# ProProject__V1_1_02_2023-12-25.net
KiCad netlist of a schematic drawn in EasyEDA Pro
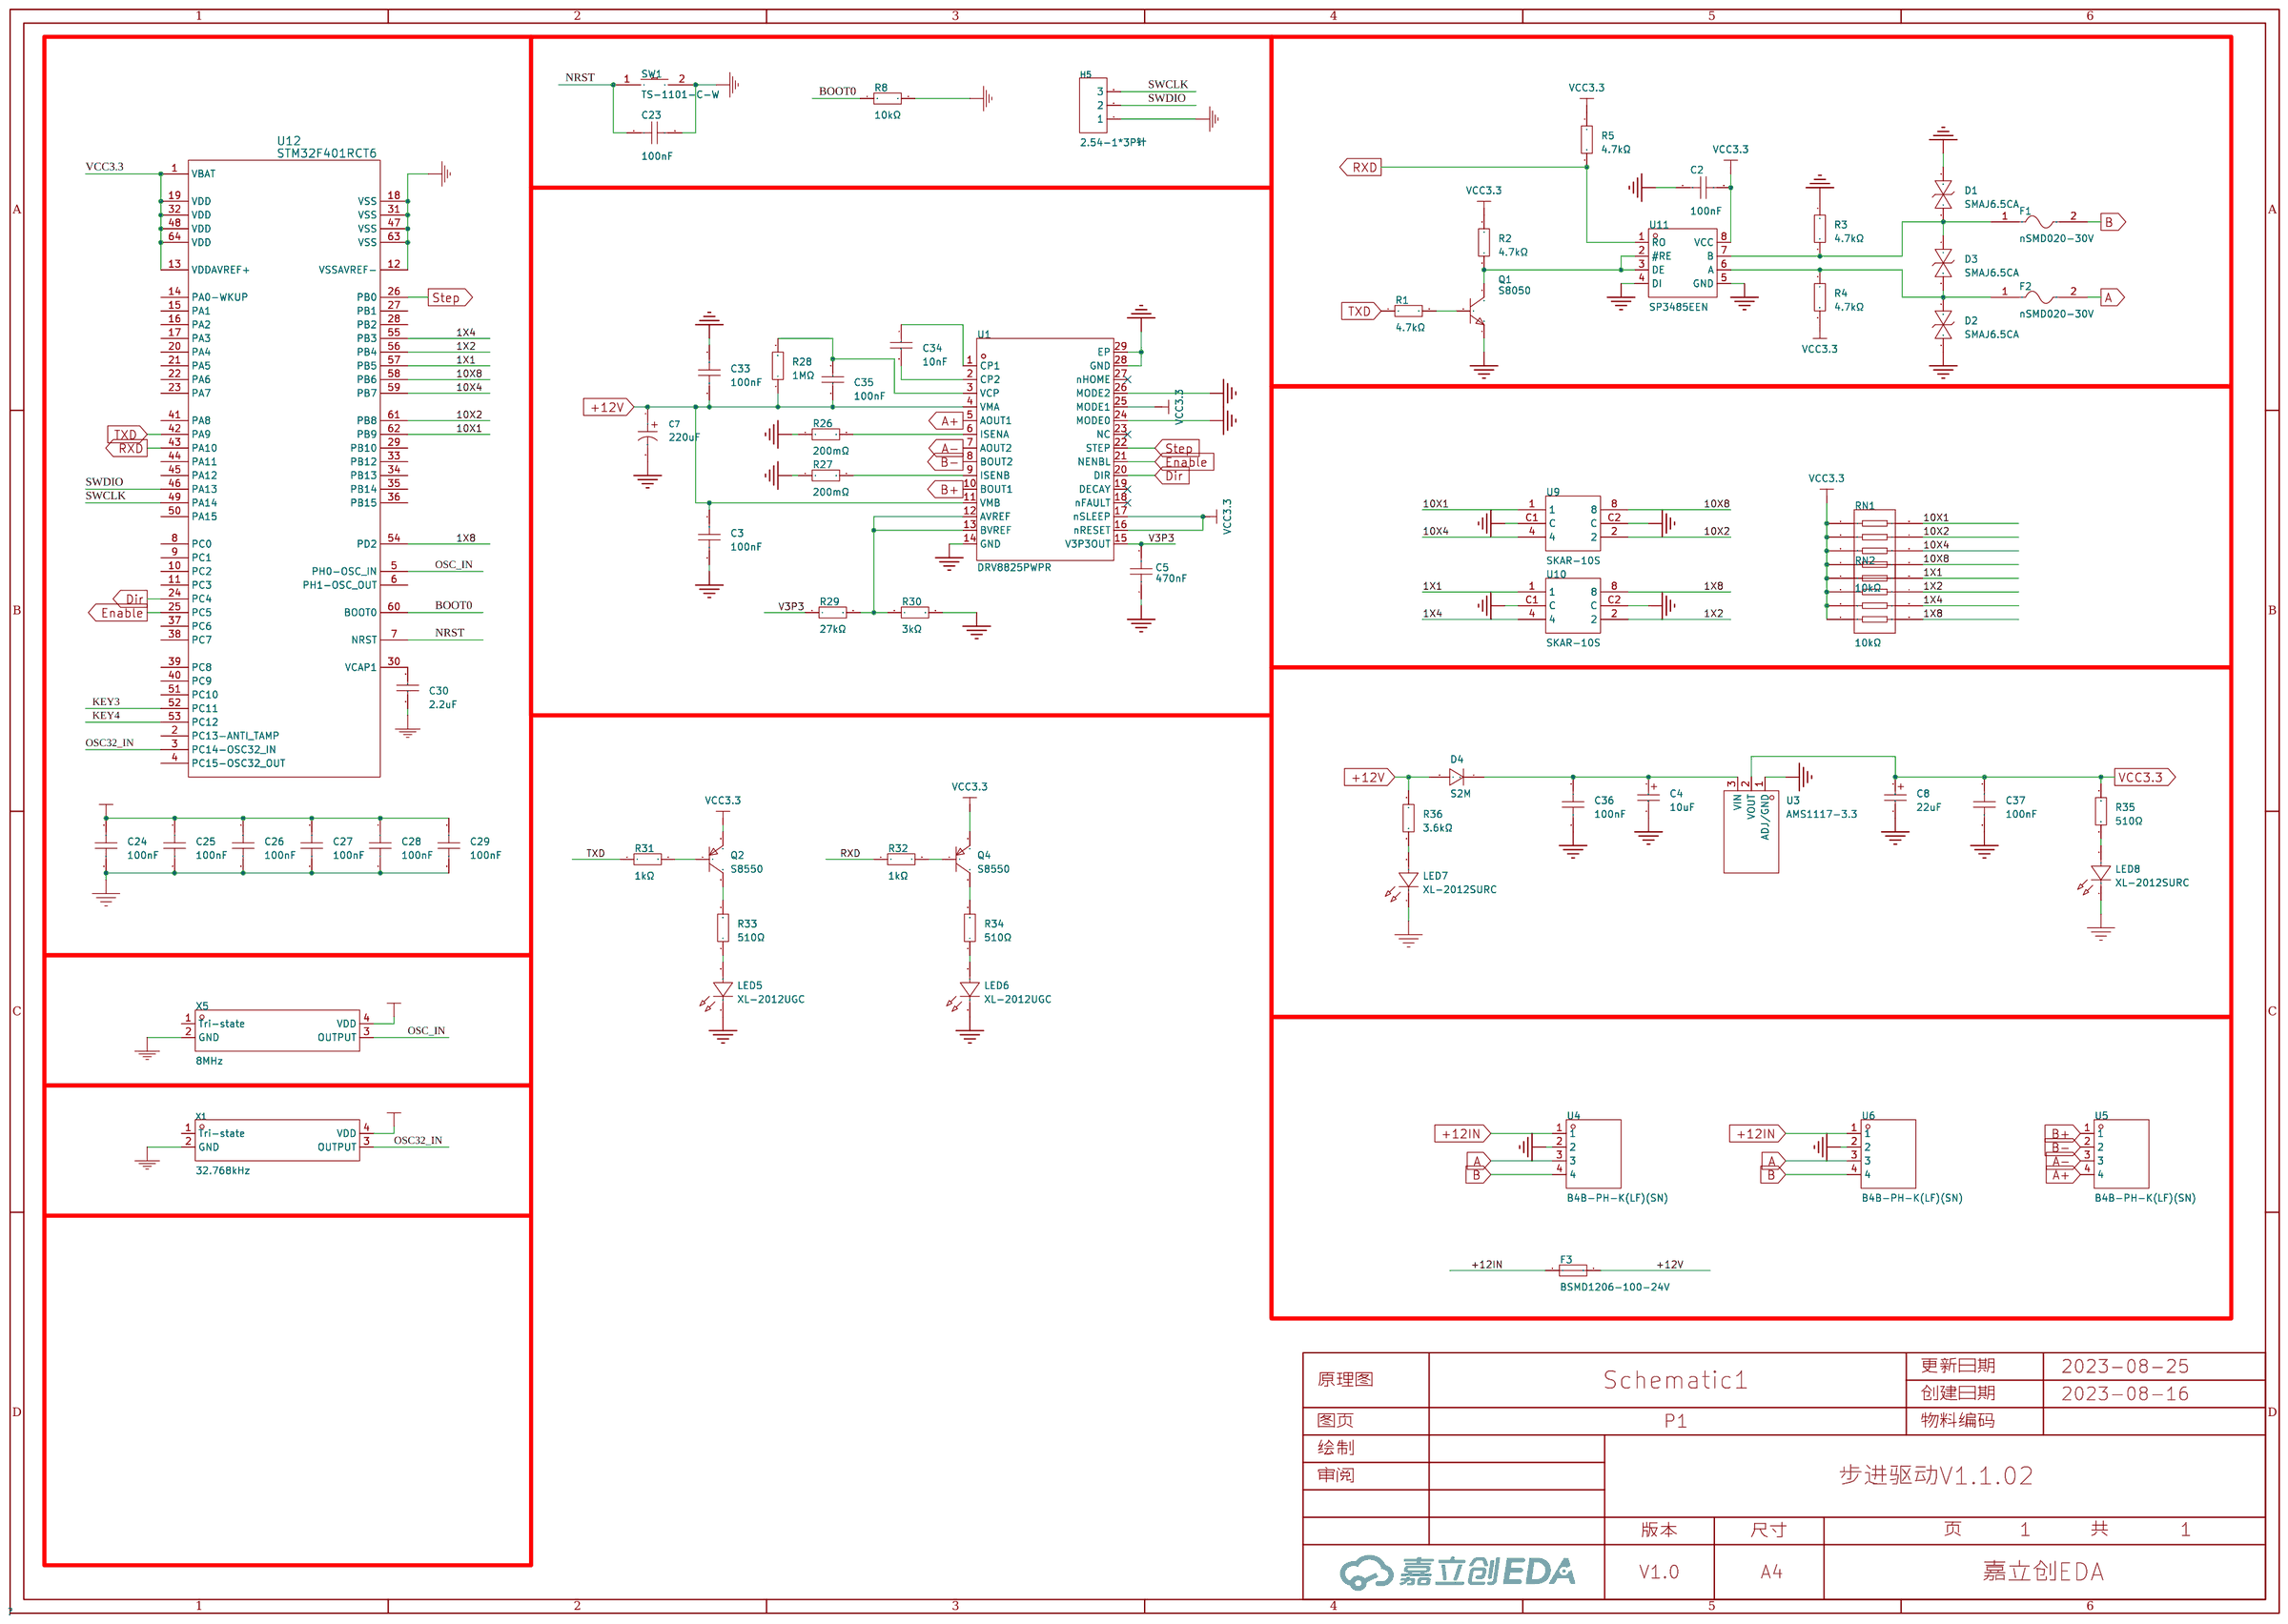
[diagram p0: schematic sheet]

(export (version "E")
  (design (tool "Eeschema 10.0.6"))
  (components
    (comp (ref "C2")
      (value "100nF")
      (footprint "easyedapro:C0603")
      (description "容值:100nF;精度:±10%;额定电压:50V;材质(温度系数):X7R;")
      (fields
        (field (name "Manufacturer Part") "CC0603KRX7R9BB104")
        (field (name "Manufacturer") "YAGEO(国巨)")
      )
      (libsource (lib "easyedapro") (part "CC0603KRX7R9BB104"))
    )
    (comp (ref "C3")
      (value "100nF")
      (footprint "easyedapro:C0603")
      (description "容值:100nF;精度:±10%;额定电压:50V;材质(温度系数):X7R;")
      (fields
        (field (name "Manufacturer Part") "CC0603KRX7R9BB104")
        (field (name "Manufacturer") "YAGEO(国巨)")
      )
      (libsource (lib "easyedapro") (part "CC0603KRX7R9BB104"))
    )
    (comp (ref "C4")
      (value "10uF")
      (footprint "easyedapro:CAP-SMD_L3.2-W1.6-RD")
      (description "容值:10uF;精度:±10%;额定电压:16V;等效串联电阻:10Ω@100kHz;")
      (fields
        (field (name "Manufacturer Part") "CA45-A-16V-10uF-K")
        (field (name "Manufacturer") "CEC(振华新云)")
      )
      (libsource (lib "easyedapro") (part "CA45-A-16V-10UF-K"))
    )
    (comp (ref "C5")
      (value "470nF")
      (footprint "easyedapro:C0603")
      (description "容值:470nF;精度:±10%;额定电压:6.3V;材质(温度系数):X5R;")
      (fields
        (field (name "Manufacturer Part") "CC0603KRX5R5BB474")
        (field (name "Manufacturer") "YAGEO(国巨)")
      )
      (libsource (lib "easyedapro") (part "CC0603KRX5R5BB474"))
    )
    (comp (ref "C7")
      (value "220uF")
      (footprint "easyedapro:CAP-SMD_BD6.3-L6.6-W6.6-FD")
      (description "容值:220uF;精度:±20%;额定电压:16V;纹波电流:110mA@120Hz;等效串联电阻:-;")
      (fields
        (field (name "Manufacturer Part") "RVT220UF16V67RV0015")
        (field (name "Manufacturer") "KNSCHA(科尼盛)")
      )
      (libsource (lib "easyedapro") (part "RVT220UF16V67RV0015"))
    )
    (comp (ref "C8")
      (value "22uF")
      (footprint "easyedapro:CAP-SMD_L3.5-W2.8-R-RD")
      (description "容值:22uF;精度:±10%;额定电压:16V;等效串联电阻:2.2Ω@100kHz;")
      (fields (field (name "Manufacturer Part") "CA45-B016K226T") (field (name "Manufacturer") "湘怡中元/湘江"))
      (libsource (lib "easyedapro") (part "CA45-B016K226T"))
    )
    (comp (ref "C23")
      (value "100nF")
      (footprint "easyedapro:C0603")
      (description "容值:100nF;精度:±10%;额定电压:50V;材质(温度系数):X7R;")
      (fields
        (field (name "Manufacturer Part") "CC0603KRX7R9BB104")
        (field (name "Manufacturer") "YAGEO(国巨)")
      )
      (libsource (lib "easyedapro") (part "CC0603KRX7R9BB104"))
    )
    (comp (ref "C24")
      (value "100nF")
      (footprint "easyedapro:C0603")
      (description "容值:100nF;精度:±10%;额定电压:50V;材质(温度系数):X7R;")
      (fields
        (field (name "Manufacturer Part") "CC0603KRX7R9BB104")
        (field (name "Manufacturer") "YAGEO(国巨)")
      )
      (libsource (lib "easyedapro") (part "CC0603KRX7R9BB104"))
    )
    (comp (ref "C25")
      (value "100nF")
      (footprint "easyedapro:C0603")
      (description "容值:100nF;精度:±10%;额定电压:50V;材质(温度系数):X7R;")
      (fields
        (field (name "Manufacturer Part") "CC0603KRX7R9BB104")
        (field (name "Manufacturer") "YAGEO(国巨)")
      )
      (libsource (lib "easyedapro") (part "CC0603KRX7R9BB104"))
    )
    (comp (ref "C26")
      (value "100nF")
      (footprint "easyedapro:C0603")
      (description "容值:100nF;精度:±10%;额定电压:50V;材质(温度系数):X7R;")
      (fields
        (field (name "Manufacturer Part") "CC0603KRX7R9BB104")
        (field (name "Manufacturer") "YAGEO(国巨)")
      )
      (libsource (lib "easyedapro") (part "CC0603KRX7R9BB104"))
    )
    (comp (ref "C27")
      (value "100nF")
      (footprint "easyedapro:C0603")
      (description "容值:100nF;精度:±10%;额定电压:50V;材质(温度系数):X7R;")
      (fields
        (field (name "Manufacturer Part") "CC0603KRX7R9BB104")
        (field (name "Manufacturer") "YAGEO(国巨)")
      )
      (libsource (lib "easyedapro") (part "CC0603KRX7R9BB104"))
    )
    (comp (ref "C28")
      (value "100nF")
      (footprint "easyedapro:C0603")
      (description "容值:100nF;精度:±10%;额定电压:50V;材质(温度系数):X7R;")
      (fields
        (field (name "Manufacturer Part") "CC0603KRX7R9BB104")
        (field (name "Manufacturer") "YAGEO(国巨)")
      )
      (libsource (lib "easyedapro") (part "CC0603KRX7R9BB104"))
    )
    (comp (ref "C29")
      (value "100nF")
      (footprint "easyedapro:C0603")
      (description "容值:100nF;精度:±10%;额定电压:50V;材质(温度系数):X7R;")
      (fields
        (field (name "Manufacturer Part") "CC0603KRX7R9BB104")
        (field (name "Manufacturer") "YAGEO(国巨)")
      )
      (libsource (lib "easyedapro") (part "CC0603KRX7R9BB104"))
    )
    (comp (ref "C30")
      (value "2.2uF")
      (footprint "easyedapro:C0603")
      (description "容值:2.2uF;精度:±10%;额定电压:25V;材质(温度系数):X7R;")
      (fields (field (name "Manufacturer Part") "0603B225K250NT") (field (name "Manufacturer") "FH(风华)"))
      (libsource (lib "easyedapro") (part "0603B225K250NT"))
    )
    (comp (ref "C33")
      (value "100nF")
      (footprint "easyedapro:C0603")
      (description "容值:100nF;精度:±10%;额定电压:50V;材质(温度系数):X7R;")
      (fields
        (field (name "Manufacturer Part") "CC0603KRX7R9BB104")
        (field (name "Manufacturer") "YAGEO(国巨)")
      )
      (libsource (lib "easyedapro") (part "CC0603KRX7R9BB104"))
    )
    (comp (ref "C34")
      (value "10nF")
      (footprint "easyedapro:C0603")
      (description "容值:10nF;精度:±10%;额定电压:50V;材质(温度系数):X7R;")
      (fields
        (field (name "Manufacturer Part") "CC0603KRX7R9BB103")
        (field (name "Manufacturer") "YAGEO(国巨)")
      )
      (libsource (lib "easyedapro") (part "CC0603KRX7R9BB103"))
    )
    (comp (ref "C35")
      (value "100nF")
      (footprint "easyedapro:C0603")
      (description "容值:100nF;精度:±10%;额定电压:16V;材质(温度系数):X7R;")
      (fields
        (field (name "Manufacturer Part") "CL10B104KO8NNNC")
        (field (name "Manufacturer") "SAMSUNG(三星)")
      )
      (libsource (lib "easyedapro") (part "CL10B104KO8NNNC"))
    )
    (comp (ref "C36")
      (value "100nF")
      (footprint "easyedapro:C0603")
      (description "容值:100nF;精度:±10%;额定电压:50V;材质(温度系数):X7R;")
      (fields
        (field (name "Manufacturer Part") "CC0603KRX7R9BB104")
        (field (name "Manufacturer") "YAGEO(国巨)")
      )
      (libsource (lib "easyedapro") (part "CC0603KRX7R9BB104"))
    )
    (comp (ref "C37")
      (value "100nF")
      (footprint "easyedapro:C0603")
      (description "容值:100nF;精度:±10%;额定电压:50V;材质(温度系数):X7R;")
      (fields
        (field (name "Manufacturer Part") "CC0603KRX7R9BB104")
        (field (name "Manufacturer") "YAGEO(国巨)")
      )
      (libsource (lib "easyedapro") (part "CC0603KRX7R9BB104"))
    )
    (comp (ref "D1")
      (value "SMAJ6.5CA")
      (footprint "easyedapro:SMA_L4.3-W2.5-LS5.0-BI")
      (description "极性:双向;")
      (fields (field (name "Manufacturer") "TWGMC(台湾迪嘉)"))
      (libsource (lib "easyedapro") (part "SMAJ6.5CA_C726773"))
    )
    (comp (ref "D2")
      (value "SMAJ6.5CA")
      (footprint "easyedapro:SMA_L4.3-W2.5-LS5.0-BI")
      (description "极性:双向;")
      (fields (field (name "Manufacturer") "TWGMC(台湾迪嘉)"))
      (libsource (lib "easyedapro") (part "SMAJ6.5CA_C726773"))
    )
    (comp (ref "D3")
      (value "SMAJ6.5CA")
      (footprint "easyedapro:SMA_L4.3-W2.5-LS5.0-BI")
      (description "极性:双向;")
      (fields (field (name "Manufacturer") "TWGMC(台湾迪嘉)"))
      (libsource (lib "easyedapro") (part "SMAJ6.5CA_C726773"))
    )
    (comp (ref "D4")
      (value "S2M")
      (footprint "easyedapro:SMA_L4.4-W2.8-LS5.4-RD")
      (description "二极管配置:-;直流反向耐压(Vr):1kV;平均整流电流(Io):2A;正向压降(Vf):1.1V@2A;反向电流(Ir):5uA@1kV;")
      (fields (field (name "Manufacturer") "MDD"))
      (libsource (lib "easyedapro") (part "S2M-C18905"))
    )
    (comp (ref "F1")
      (value "nSMD020-30V")
      (footprint "easyedapro:F1206")
      (description "最大电压:30V;最大电流:100A;保持电流:200mA;跳闸电流:460mA;")
      (fields (field (name "Manufacturer") "台湾陆海"))
      (libsource (lib "easyedapro") (part "nSMD020-30V"))
    )
    (comp (ref "F2")
      (value "nSMD020-30V")
      (footprint "easyedapro:F1206")
      (description "最大电压:30V;最大电流:100A;保持电流:200mA;跳闸电流:460mA;")
      (fields (field (name "Manufacturer") "台湾陆海"))
      (libsource (lib "easyedapro") (part "nSMD020-30V"))
    )
    (comp (ref "F3")
      (value "BSMD1206-100-24V")
      (footprint "easyedapro:F1206")
      (fields (field (name "Manufacturer") "BHFUSE(佰宏)"))
      (libsource (lib "easyedapro") (part "BSMD1206-100-24V"))
    )
    (comp (ref "H5")
      (value "2.54-1*3P针")
      (footprint "easyedapro:HDR-TH_3P-P2.54-V-M-1")
      (fields (field (name "Manufacturer") "BOOMELE(博穆精密)"))
      (libsource (lib "easyedapro") (part "Header-Male-2.54_1x3"))
    )
    (comp (ref "LED5")
      (value "XL-2012UGC")
      (footprint "easyedapro:LED0805-RD_GREEN")
      (description "发光颜色:翠绿;主波长:516nm~525nm;色温:-;功率:80mW;安装方式:正贴;")
      (fields (field (name "Manufacturer") "XINGLIGHT(成兴光)"))
      (libsource (lib "easyedapro") (part "XL-2012UGC"))
    )
    (comp (ref "LED6")
      (value "XL-2012UGC")
      (footprint "easyedapro:LED0805-RD_GREEN")
      (description "发光颜色:翠绿;主波长:516nm~525nm;色温:-;功率:80mW;安装方式:正贴;")
      (fields (field (name "Manufacturer") "XINGLIGHT(成兴光)"))
      (libsource (lib "easyedapro") (part "XL-2012UGC"))
    )
    (comp (ref "LED7")
      (value "XL-2012SURC")
      (footprint "easyedapro:LED0805-RD_RED")
      (description "发光颜色:红灯;主波长:617nm~621nm;色温:-;功率:55mW;安装方式:正贴;")
      (fields (field (name "Manufacturer") "XINGLIGHT(成兴光)"))
      (libsource (lib "easyedapro") (part "XL-2012SURC"))
    )
    (comp (ref "LED8")
      (value "XL-2012SURC")
      (footprint "easyedapro:LED0805-RD_RED")
      (description "发光颜色:红灯;主波长:617nm~621nm;色温:-;功率:55mW;安装方式:正贴;")
      (fields (field (name "Manufacturer") "XINGLIGHT(成兴光)"))
      (libsource (lib "easyedapro") (part "XL-2012SURC"))
    )
    (comp (ref "Q1")
      (value "S8050")
      (footprint "easyedapro:SOT-23-3_L2.9-W1.6-P1.90-LS2.8-BR")
      (description "晶体管类型:NPN;集射极击穿电压(Vceo):25V;集电极电流(Ic):500mA;功率(Pd):300mW;直流电流增益(hFE@Ic,Vce):120@50mA,1V;")
      (fields (field (name "Manufacturer") "CJ(江苏长电/长晶)"))
      (libsource (lib "easyedapro") (part "S8050_C105433"))
    )
    (comp (ref "Q2")
      (value "S8550")
      (footprint "easyedapro:SOT-23-3_L2.9-W1.6-P1.90-LS2.8-BR")
      (description "晶体管类型:PNP;集射极击穿电压(Vceo):25V;集电极电流(Ic):500mA;功率(Pd):300mW;直流电流增益(hFE@Ic,Vce):120@50mA,1V;")
      (fields (field (name "Manufacturer") "CJ(江苏长电/长晶)"))
      (libsource (lib "easyedapro") (part "S8550_C105432"))
    )
    (comp (ref "Q4")
      (value "S8550")
      (footprint "easyedapro:SOT-23-3_L2.9-W1.6-P1.90-LS2.8-BR")
      (description "晶体管类型:PNP;集射极击穿电压(Vceo):25V;集电极电流(Ic):500mA;功率(Pd):300mW;直流电流增益(hFE@Ic,Vce):120@50mA,1V;")
      (fields (field (name "Manufacturer") "CJ(江苏长电/长晶)"))
      (libsource (lib "easyedapro") (part "S8550_C105432"))
    )
    (comp (ref "R1")
      (value "4.7kΩ")
      (footprint "easyedapro:R0603")
      (description "电阻类型:厚膜电阻;阻值:4.7kΩ;精度:±1%;功率:100mW;")
      (fields
        (field (name "Manufacturer Part") "0603WAF4701T5E")
        (field (name "Manufacturer") "UNI-ROYAL(厚声)")
      )
      (libsource (lib "easyedapro") (part "0603WAF4701T5E"))
    )
    (comp (ref "R2")
      (value "4.7kΩ")
      (footprint "easyedapro:R0603")
      (description "电阻类型:厚膜电阻;阻值:4.7kΩ;精度:±1%;功率:100mW;")
      (fields
        (field (name "Manufacturer Part") "0603WAF4701T5E")
        (field (name "Manufacturer") "UNI-ROYAL(厚声)")
      )
      (libsource (lib "easyedapro") (part "0603WAF4701T5E"))
    )
    (comp (ref "R3")
      (value "4.7kΩ")
      (footprint "easyedapro:R0603")
      (description "电阻类型:厚膜电阻;阻值:4.7kΩ;精度:±1%;功率:100mW;")
      (fields
        (field (name "Manufacturer Part") "0603WAF4701T5E")
        (field (name "Manufacturer") "UNI-ROYAL(厚声)")
      )
      (libsource (lib "easyedapro") (part "0603WAF4701T5E"))
    )
    (comp (ref "R4")
      (value "4.7kΩ")
      (footprint "easyedapro:R0603")
      (description "电阻类型:厚膜电阻;阻值:4.7kΩ;精度:±1%;功率:100mW;")
      (fields
        (field (name "Manufacturer Part") "0603WAF4701T5E")
        (field (name "Manufacturer") "UNI-ROYAL(厚声)")
      )
      (libsource (lib "easyedapro") (part "0603WAF4701T5E"))
    )
    (comp (ref "R5")
      (value "4.7kΩ")
      (footprint "easyedapro:R0603")
      (description "电阻类型:厚膜电阻;阻值:4.7kΩ;精度:±1%;功率:100mW;")
      (fields
        (field (name "Manufacturer Part") "0603WAF4701T5E")
        (field (name "Manufacturer") "UNI-ROYAL(厚声)")
      )
      (libsource (lib "easyedapro") (part "0603WAF4701T5E"))
    )
    (comp (ref "R8")
      (value "10kΩ")
      (footprint "easyedapro:R0603")
      (description "电阻类型:厚膜电阻;阻值:10kΩ;精度:±1%;功率:100mW;")
      (fields
        (field (name "Manufacturer Part") "0603WAF1002T5E")
        (field (name "Manufacturer") "UNI-ROYAL(厚声)")
      )
      (libsource (lib "easyedapro") (part "0603WAF1002T5E"))
    )
    (comp (ref "R26")
      (value "200mΩ")
      (footprint "easyedapro:R0603")
      (description "电阻类型:厚膜电阻;阻值:200mΩ;精度:±1%;功率:100mW;")
      (fields
        (field (name "Manufacturer Part") "0603WAF200LT5E")
        (field (name "Manufacturer") "UNI-ROYAL(厚声)")
      )
      (libsource (lib "easyedapro") (part "0603WAF200LT5E"))
    )
    (comp (ref "R27")
      (value "200mΩ")
      (footprint "easyedapro:R0603")
      (description "电阻类型:厚膜电阻;阻值:200mΩ;精度:±1%;功率:100mW;")
      (fields
        (field (name "Manufacturer Part") "0603WAF200LT5E")
        (field (name "Manufacturer") "UNI-ROYAL(厚声)")
      )
      (libsource (lib "easyedapro") (part "0603WAF200LT5E"))
    )
    (comp (ref "R28")
      (value "1MΩ")
      (footprint "easyedapro:R0603")
      (description "电阻类型:厚膜电阻;阻值:1MΩ;精度:±1%;功率:100mW;")
      (fields
        (field (name "Manufacturer Part") "0603WAF1004T5E")
        (field (name "Manufacturer") "UNI-ROYAL(厚声)")
      )
      (libsource (lib "easyedapro") (part "0603WAF1004T5E"))
    )
    (comp (ref "R29")
      (value "27kΩ")
      (footprint "easyedapro:R0603")
      (description "电阻类型:厚膜电阻;阻值:27kΩ;精度:±1%;功率:100mW;")
      (fields
        (field (name "Manufacturer Part") "0603WAF2702T5E")
        (field (name "Manufacturer") "UNI-ROYAL(厚声)")
      )
      (libsource (lib "easyedapro") (part "0603WAF2702T5E"))
    )
    (comp (ref "R30")
      (value "3kΩ")
      (footprint "easyedapro:R0603")
      (description "电阻类型:厚膜电阻;阻值:3kΩ;精度:±1%;功率:100mW;")
      (fields
        (field (name "Manufacturer Part") "0603WAF3001T5E")
        (field (name "Manufacturer") "UNI-ROYAL(厚声)")
      )
      (libsource (lib "easyedapro") (part "0603WAF3001T5E"))
    )
    (comp (ref "R31")
      (value "1kΩ")
      (footprint "easyedapro:R0603")
      (description "电阻类型:厚膜电阻;阻值:1kΩ;精度:±1%;功率:100mW;")
      (fields
        (field (name "Manufacturer Part") "0603WAF1001T5E")
        (field (name "Manufacturer") "UNI-ROYAL(厚声)")
      )
      (libsource (lib "easyedapro") (part "0603WAF1001T5E"))
    )
    (comp (ref "R32")
      (value "1kΩ")
      (footprint "easyedapro:R0603")
      (description "电阻类型:厚膜电阻;阻值:1kΩ;精度:±1%;功率:100mW;")
      (fields
        (field (name "Manufacturer Part") "0603WAF1001T5E")
        (field (name "Manufacturer") "UNI-ROYAL(厚声)")
      )
      (libsource (lib "easyedapro") (part "0603WAF1001T5E"))
    )
    (comp (ref "R33")
      (value "510Ω")
      (footprint "easyedapro:R0603")
      (description "电阻类型:厚膜电阻;阻值:510Ω;精度:±1%;功率:100mW;")
      (fields
        (field (name "Manufacturer Part") "0603WAF5100T5E")
        (field (name "Manufacturer") "UNI-ROYAL(厚声)")
      )
      (libsource (lib "easyedapro") (part "0603WAF5100T5E"))
    )
    (comp (ref "R34")
      (value "510Ω")
      (footprint "easyedapro:R0603")
      (description "电阻类型:厚膜电阻;阻值:510Ω;精度:±1%;功率:100mW;")
      (fields
        (field (name "Manufacturer Part") "0603WAF5100T5E")
        (field (name "Manufacturer") "UNI-ROYAL(厚声)")
      )
      (libsource (lib "easyedapro") (part "0603WAF5100T5E"))
    )
    (comp (ref "R35")
      (value "510Ω")
      (footprint "easyedapro:R0603")
      (description "电阻类型:厚膜电阻;阻值:510Ω;精度:±1%;功率:100mW;")
      (fields
        (field (name "Manufacturer Part") "0603WAF5100T5E")
        (field (name "Manufacturer") "UNI-ROYAL(厚声)")
      )
      (libsource (lib "easyedapro") (part "0603WAF5100T5E"))
    )
    (comp (ref "R36")
      (value "3.6kΩ")
      (footprint "easyedapro:R0603")
      (description "电阻类型:厚膜电阻;阻值:3.6kΩ;精度:±1%;功率:100mW;")
      (fields
        (field (name "Manufacturer Part") "0603WAF3601T5E")
        (field (name "Manufacturer") "UNI-ROYAL(厚声)")
      )
      (libsource (lib "easyedapro") (part "0603WAF3601T5E"))
    )
    (comp (ref "RN1")
      (value "10kΩ")
      (footprint "easyedapro:RES-ARRAY-SMD_0603-8P-L3.2-W1.6-BL")
      (description "阻值:10kΩ;精度:±5%;单个元件功率:62.5mW;电阻器数:4;")
      (fields
        (field (name "Manufacturer Part") "4D03WGJ0103T5E")
        (field (name "Manufacturer") "UNI-ROYAL(厚声)")
      )
      (libsource (lib "easyedapro") (part "4D03WGJ0103T5E"))
    )
    (comp (ref "RN2")
      (value "10kΩ")
      (footprint "easyedapro:RES-ARRAY-SMD_0603-8P-L3.2-W1.6-BL")
      (description "阻值:10kΩ;精度:±5%;单个元件功率:62.5mW;电阻器数:4;")
      (fields
        (field (name "Manufacturer Part") "4D03WGJ0103T5E")
        (field (name "Manufacturer") "UNI-ROYAL(厚声)")
      )
      (libsource (lib "easyedapro") (part "4D03WGJ0103T5E"))
    )
    (comp (ref "SW1")
      (value "TS-1101-C-W")
      (footprint "easyedapro:SW-SMD_L6.0-W3.3-LS8.0")
      (description "触点电流:50mA;额定电压(AC):-;额定电压(DC):12V;额定功率:-;绝缘电阻:-;电路结构:单刀单掷;安装方式:立贴;带灯:无;作用力:260gf;机械寿命:5万次;带支架:否;")
      (fields (field (name "Manufacturer") "XKB Connectivity(中国星坤)"))
      (libsource (lib "easyedapro") (part "TS-1101-C-W"))
    )
    (comp (ref "U1")
      (value "DRV8825PWPR")
      (footprint "easyedapro:HTSSOP-28_L9.7-W4.4-P0.65-LS6.4-BL-EP")
      (description "类型:-;电源电压:8.2V~45V;输出电流:2.5A;接口:-;")
      (fields (field (name "Manufacturer") "TI(德州仪器)"))
      (libsource (lib "easyedapro") (part "DRV8825PWPR"))
    )
    (comp (ref "U3")
      (value "AMS1117-3.3")
      (footprint "easyedapro:SOT-89-3_L4.5-W2.5-P1.50-LS4.2-BR")
      (description "输出类型:-;")
      (fields (field (name "Manufacturer") "Slkor(萨科微)"))
      (libsource (lib "easyedapro") (part "AMS1117-3.3_C880752"))
    )
    (comp (ref "U4")
      (value "B4B-PH-K(LF)(SN)")
      (footprint "easyedapro:CONN-TH_B4B-PH-K-LF-SN")
      (description "参考系列:PH;间距:2mm;插针结构:1x4P;排数:1;每排PIN数:4;行距:-;安装方式:-;触头材质:黄铜;")
      (fields (field (name "Manufacturer") "JST"))
      (libsource (lib "easyedapro") (part "B4B-PH-K(LF)(SN)"))
    )
    (comp (ref "U5")
      (value "B4B-PH-K(LF)(SN)")
      (footprint "easyedapro:CONN-TH_B4B-PH-K-LF-SN")
      (description "参考系列:PH;间距:2mm;插针结构:1x4P;排数:1;每排PIN数:4;行距:-;安装方式:-;触头材质:黄铜;")
      (fields (field (name "Manufacturer") "JST"))
      (libsource (lib "easyedapro") (part "B4B-PH-K(LF)(SN)"))
    )
    (comp (ref "U6")
      (value "B4B-PH-K(LF)(SN)")
      (footprint "easyedapro:CONN-TH_B4B-PH-K-LF-SN")
      (description "参考系列:PH;间距:2mm;插针结构:1x4P;排数:1;每排PIN数:4;行距:-;安装方式:-;触头材质:黄铜;")
      (fields (field (name "Manufacturer") "JST"))
      (libsource (lib "easyedapro") (part "B4B-PH-K(LF)(SN)"))
    )
    (comp (ref "U9")
      (value "SKAR-10S")
      (footprint "easyedapro:SW-SMD_SKAR-10S")
      (description "类型:贴片型;")
      (fields (field (name "Manufacturer") "SM Switch"))
      (libsource (lib "easyedapro") (part "SKAR-10S"))
    )
    (comp (ref "U10")
      (value "SKAR-10S")
      (footprint "easyedapro:SW-SMD_SKAR-10S")
      (description "类型:贴片型;")
      (fields (field (name "Manufacturer") "SM Switch"))
      (libsource (lib "easyedapro") (part "SKAR-10S"))
    )
    (comp (ref "U11")
      (value "SP3485EEN")
      (footprint "easyedapro:SOP-8_L5.0-W4.0-P1.27-LS6.0-BL")
      (fields (field (name "Manufacturer") "UMW(广东友台半导体)"))
      (libsource (lib "easyedapro") (part "SP3485EEN"))
    )
    (comp (ref "U12")
      (value "STM32F401RCT6")
      (footprint "easyedapro:LQFP-64_L10.0-W10.0-P0.50-LS12.0-BL")
      (fields (field (name "Manufacturer") "STMicroelectronics"))
      (libsource (lib "easyedapro") (part "STM32F401RCT6"))
    )
    (comp (ref "X1")
      (value "32.768kHz")
      (footprint "easyedapro:OSC-SMD_4P-L3.2-W2.5-BL_SIT8008BI")
      (description "频率:32.768kHz;频率稳定度:±20ppm;工作电压:3.3V;输出模式:CMOS;")
      (fields
        (field (name "Manufacturer Part") "S3D32.768KB20F30T")
        (field (name "Manufacturer") "SCTF(星通时频)")
      )
      (libsource (lib "easyedapro") (part "S3D32.768KB20F30T"))
    )
    (comp (ref "X5")
      (value "8MHz")
      (footprint "easyedapro:OSC-SMD_4P-L3.2-W2.5-BL")
      (description "频率:8MHz;频率稳定度:±10ppm;工作电压:1.8V~3.3V;")
      (fields (field (name "Manufacturer Part") "OT32258MJBA4SL") (field (name "Manufacturer") "YXC(扬兴晶振)"))
      (libsource (lib "easyedapro") (part "OT32258MJBA4SL"))
    )
  )
  (nets
    (net (code "1") (name "+12IN") (class "Default")
      (node (ref "F3") (pin "1") (pinfunction "1_1") (pintype "input"))
      (node (ref "U4") (pin "1") (pinfunction "1_1") (pintype "input"))
      (node (ref "U6") (pin "1") (pinfunction "1_1") (pintype "input"))
    )
    (net (code "2") (name "+12V") (class "Default")
      (node (ref "C3") (pin "1") (pinfunction "1_1") (pintype "input"))
      (node (ref "C33") (pin "2") (pinfunction "2_2") (pintype "input"))
      (node (ref "C35") (pin "2") (pinfunction "2_2") (pintype "input"))
      (node (ref "C7") (pin "1") (pinfunction "1_1") (pintype "input"))
      (node (ref "D4") (pin "2") (pinfunction "A_2") (pintype "input"))
      (node (ref "F3") (pin "2") (pinfunction "2_2") (pintype "input"))
      (node (ref "R28") (pin "1") (pinfunction "1_1") (pintype "input"))
      (node (ref "R36") (pin "1") (pinfunction "1_1") (pintype "input"))
      (node (ref "U1") (pin "11") (pinfunction "VMB_11") (pintype "input"))
      (node (ref "U1") (pin "4") (pinfunction "VMA_4") (pintype "input"))
    )
    (net (code "3") (name "/1X1") (class "Default")
      (node (ref "RN2") (pin "8") (pinfunction "8_8") (pintype "input"))
      (node (ref "U10") (pin "1") (pinfunction "1_1") (pintype "input"))
      (node (ref "U12") (pin "57") (pinfunction "PB5_57") (pintype "bidirectional"))
    )
    (net (code "4") (name "/1X2") (class "Default")
      (node (ref "RN2") (pin "7") (pinfunction "7_7") (pintype "input"))
      (node (ref "U10") (pin "2") (pinfunction "2_2") (pintype "input"))
      (node (ref "U12") (pin "56") (pinfunction "PB4_56") (pintype "bidirectional"))
    )
    (net (code "5") (name "/1X4") (class "Default")
      (node (ref "RN2") (pin "6") (pinfunction "6_6") (pintype "input"))
      (node (ref "U10") (pin "4") (pinfunction "4_4") (pintype "input"))
      (node (ref "U12") (pin "55") (pinfunction "PB3_55") (pintype "bidirectional"))
    )
    (net (code "6") (name "/1X8") (class "Default")
      (node (ref "RN2") (pin "5") (pinfunction "5_5") (pintype "input"))
      (node (ref "U10") (pin "8") (pinfunction "8_8") (pintype "input"))
      (node (ref "U12") (pin "54") (pinfunction "PD2_54") (pintype "bidirectional"))
    )
    (net (code "7") (name "/10X1") (class "Default")
      (node (ref "RN1") (pin "8") (pinfunction "8_8") (pintype "input"))
      (node (ref "U12") (pin "62") (pinfunction "PB9_62") (pintype "bidirectional"))
      (node (ref "U9") (pin "1") (pinfunction "1_1") (pintype "input"))
    )
    (net (code "8") (name "/10X2") (class "Default")
      (node (ref "RN1") (pin "7") (pinfunction "7_7") (pintype "input"))
      (node (ref "U12") (pin "61") (pinfunction "PB8_61") (pintype "bidirectional"))
      (node (ref "U9") (pin "2") (pinfunction "2_2") (pintype "input"))
    )
    (net (code "9") (name "/10X4") (class "Default")
      (node (ref "RN1") (pin "6") (pinfunction "6_6") (pintype "input"))
      (node (ref "U12") (pin "59") (pinfunction "PB7_59") (pintype "bidirectional"))
      (node (ref "U9") (pin "4") (pinfunction "4_4") (pintype "input"))
    )
    (net (code "10") (name "/10X8") (class "Default")
      (node (ref "RN1") (pin "5") (pinfunction "5_5") (pintype "input"))
      (node (ref "U12") (pin "58") (pinfunction "PB6_58") (pintype "bidirectional"))
      (node (ref "U9") (pin "8") (pinfunction "8_8") (pintype "input"))
    )
    (net (code "11") (name "/BOOT0") (class "Default")
      (node (ref "R8") (pin "1") (pinfunction "1_1") (pintype "input"))
      (node (ref "U12") (pin "60") (pinfunction "BOOT0_60") (pintype "input"))
    )
    (net (code "12") (name "/KEY3") (class "Default")
      (node (ref "U12") (pin "52") (pinfunction "PC11_52") (pintype "bidirectional"))
    )
    (net (code "13") (name "/KEY4") (class "Default")
      (node (ref "U12") (pin "53") (pinfunction "PC12_53") (pintype "bidirectional"))
    )
    (net (code "14") (name "/NRST") (class "Default")
      (node (ref "C23") (pin "1") (pinfunction "1_1") (pintype "input"))
      (node (ref "SW1") (pin "1") (pinfunction "1_1") (pintype "input"))
      (node (ref "U12") (pin "7") (pinfunction "NRST_7") (pintype "bidirectional"))
    )
    (net (code "15") (name "/OSC32_IN") (class "Default")
      (node (ref "U12") (pin "3") (pinfunction "PC14-OSC32_IN_3") (pintype "bidirectional"))
      (node (ref "X1") (pin "3") (pinfunction "OUTPUT_3") (pintype "input"))
    )
    (net (code "16") (name "/OSC_IN") (class "Default")
      (node (ref "U12") (pin "5") (pinfunction "PH0-OSC_IN_5") (pintype "bidirectional"))
      (node (ref "X5") (pin "3") (pinfunction "OUTPUT_3") (pintype "input"))
    )
    (net (code "17") (name "/SWCLK") (class "Default")
      (node (ref "H5") (pin "3") (pinfunction "3_3") (pintype "input"))
      (node (ref "U12") (pin "49") (pinfunction "PA14_49") (pintype "bidirectional"))
    )
    (net (code "18") (name "/SWDIO") (class "Default")
      (node (ref "H5") (pin "2") (pinfunction "2_2") (pintype "input"))
      (node (ref "U12") (pin "46") (pinfunction "PA13_46") (pintype "bidirectional"))
    )
    (net (code "19") (name "/V3P3") (class "Default")
      (node (ref "C5") (pin "2") (pinfunction "2_2") (pintype "input"))
      (node (ref "R29") (pin "1") (pinfunction "1_1") (pintype "input"))
      (node (ref "U1") (pin "15") (pinfunction "V3P3OUT_15") (pintype "input"))
    )
    (net (code "20") (name "A") (class "Default")
      (node (ref "F2") (pin "2") (pinfunction "2_2") (pintype "input"))
      (node (ref "U4") (pin "3") (pinfunction "3_3") (pintype "input"))
      (node (ref "U6") (pin "3") (pinfunction "3_3") (pintype "input"))
    )
    (net (code "21") (name "A+") (class "Default")
      (node (ref "U1") (pin "5") (pinfunction "AOUT1_5") (pintype "input"))
      (node (ref "U5") (pin "4") (pinfunction "4_4") (pintype "input"))
    )
    (net (code "22") (name "A-") (class "Default")
      (node (ref "U1") (pin "7") (pinfunction "AOUT2_7") (pintype "input"))
      (node (ref "U5") (pin "3") (pinfunction "3_3") (pintype "input"))
    )
    (net (code "23") (name "B") (class "Default")
      (node (ref "F1") (pin "2") (pinfunction "2_2") (pintype "input"))
      (node (ref "U4") (pin "4") (pinfunction "4_4") (pintype "input"))
      (node (ref "U6") (pin "4") (pinfunction "4_4") (pintype "input"))
    )
    (net (code "24") (name "B+") (class "Default")
      (node (ref "U1") (pin "10") (pinfunction "BOUT1_10") (pintype "input"))
      (node (ref "U5") (pin "1") (pinfunction "1_1") (pintype "input"))
    )
    (net (code "25") (name "B-") (class "Default")
      (node (ref "U1") (pin "8") (pinfunction "BOUT2_8") (pintype "input"))
      (node (ref "U5") (pin "2") (pinfunction "2_2") (pintype "input"))
    )
    (net (code "26") (name "Dir") (class "Default")
      (node (ref "U1") (pin "20") (pinfunction "DIR_20") (pintype "input"))
      (node (ref "U12") (pin "24") (pinfunction "PC4_24") (pintype "bidirectional"))
    )
    (net (code "27") (name "Enable") (class "Default")
      (node (ref "U1") (pin "21") (pinfunction "NENBL_21") (pintype "input"))
      (node (ref "U12") (pin "25") (pinfunction "PC5_25") (pintype "bidirectional"))
    )
    (net (code "28") (name "GND") (class "Default")
      (node (ref "C2") (pin "1") (pinfunction "1_1") (pintype "input"))
      (node (ref "C23") (pin "2") (pinfunction "2_2") (pintype "input"))
      (node (ref "C24") (pin "2") (pinfunction "2_2") (pintype "input"))
      (node (ref "C25") (pin "2") (pinfunction "2_2") (pintype "input"))
      (node (ref "C26") (pin "2") (pinfunction "2_2") (pintype "input"))
      (node (ref "C27") (pin "2") (pinfunction "2_2") (pintype "input"))
      (node (ref "C28") (pin "2") (pinfunction "2_2") (pintype "input"))
      (node (ref "C29") (pin "2") (pinfunction "2_2") (pintype "input"))
      (node (ref "C3") (pin "2") (pinfunction "2_2") (pintype "input"))
      (node (ref "C30") (pin "1") (pinfunction "1_1") (pintype "input"))
      (node (ref "C33") (pin "1") (pinfunction "1_1") (pintype "input"))
      (node (ref "C36") (pin "2") (pinfunction "2_2") (pintype "input"))
      (node (ref "C37") (pin "2") (pinfunction "2_2") (pintype "input"))
      (node (ref "C4") (pin "2") (pinfunction "2_2") (pintype "input"))
      (node (ref "C5") (pin "1") (pinfunction "1_1") (pintype "input"))
      (node (ref "C7") (pin "2") (pinfunction "2_2") (pintype "input"))
      (node (ref "C8") (pin "2") (pinfunction "2_2") (pintype "input"))
      (node (ref "D1") (pin "1") (pinfunction "1_1") (pintype "input"))
      (node (ref "D2") (pin "2") (pinfunction "2_2") (pintype "input"))
      (node (ref "H5") (pin "1") (pinfunction "1_1") (pintype "input"))
      (node (ref "LED5") (pin "1") (pinfunction "K_1") (pintype "input"))
      (node (ref "LED6") (pin "1") (pinfunction "K_1") (pintype "input"))
      (node (ref "LED7") (pin "1") (pinfunction "K_1") (pintype "input"))
      (node (ref "LED8") (pin "1") (pinfunction "K_1") (pintype "input"))
      (node (ref "Q1") (pin "2") (pinfunction "2_2") (pintype "input"))
      (node (ref "R26") (pin "1") (pinfunction "1_1") (pintype "input"))
      (node (ref "R27") (pin "1") (pinfunction "1_1") (pintype "input"))
      (node (ref "R3") (pin "1") (pinfunction "1_1") (pintype "input"))
      (node (ref "R30") (pin "2") (pinfunction "2_2") (pintype "input"))
      (node (ref "R8") (pin "2") (pinfunction "2_2") (pintype "input"))
      (node (ref "SW1") (pin "2") (pinfunction "2_2") (pintype "input"))
      (node (ref "U1") (pin "14") (pinfunction "GND_14") (pintype "input"))
      (node (ref "U1") (pin "24") (pinfunction "MODE0_24") (pintype "input"))
      (node (ref "U1") (pin "26") (pinfunction "MODE2_26") (pintype "input"))
      (node (ref "U1") (pin "28") (pinfunction "GND_28") (pintype "input"))
      (node (ref "U1") (pin "29") (pinfunction "EP_29") (pintype "input"))
      (node (ref "U10") (pin "C1") (pinfunction "C_C1") (pintype "input"))
      (node (ref "U10") (pin "C2") (pinfunction "C_C2") (pintype "input"))
      (node (ref "U11") (pin "4") (pinfunction "DI_4") (pintype "input"))
      (node (ref "U11") (pin "5") (pinfunction "GND_5") (pintype "input"))
      (node (ref "U12") (pin "12") (pinfunction "VSSAVREF-_12") (pintype "input"))
      (node (ref "U12") (pin "18") (pinfunction "VSS_18") (pintype "input"))
      (node (ref "U12") (pin "31") (pinfunction "VSS_31") (pintype "input"))
      (node (ref "U12") (pin "47") (pinfunction "VSS_47") (pintype "input"))
      (node (ref "U12") (pin "63") (pinfunction "VSS_63") (pintype "input"))
      (node (ref "U3") (pin "1") (pinfunction "ADJ/GND_1") (pintype "input"))
      (node (ref "U4") (pin "2") (pinfunction "2_2") (pintype "input"))
      (node (ref "U6") (pin "2") (pinfunction "2_2") (pintype "input"))
      (node (ref "U9") (pin "C1") (pinfunction "C_C1") (pintype "input"))
      (node (ref "U9") (pin "C2") (pinfunction "C_C2") (pintype "input"))
      (node (ref "X1") (pin "2") (pinfunction "GND_2") (pintype "input"))
      (node (ref "X5") (pin "2") (pinfunction "GND_2") (pintype "input"))
    )
    (net (code "29") (name "Net-(D4-C)") (class "Default")
      (node (ref "C36") (pin "1") (pinfunction "1_1") (pintype "input"))
      (node (ref "C4") (pin "1") (pinfunction "1_1") (pintype "input"))
      (node (ref "D4") (pin "1") (pinfunction "C_1") (pintype "input"))
      (node (ref "U3") (pin "3") (pinfunction "VIN_3") (pintype "input"))
    )
    (net (code "30") (name "Net-(LED5-A)") (class "Default")
      (node (ref "LED5") (pin "2") (pinfunction "A_2") (pintype "input"))
      (node (ref "R33") (pin "1") (pinfunction "1_1") (pintype "input"))
    )
    (net (code "31") (name "Net-(LED6-A)") (class "Default")
      (node (ref "LED6") (pin "2") (pinfunction "A_2") (pintype "input"))
      (node (ref "R34") (pin "1") (pinfunction "1_1") (pintype "input"))
    )
    (net (code "32") (name "Net-(LED7-A)") (class "Default")
      (node (ref "LED7") (pin "2") (pinfunction "A_2") (pintype "input"))
      (node (ref "R36") (pin "2") (pinfunction "2_2") (pintype "input"))
    )
    (net (code "33") (name "Net-(LED8-A)") (class "Default")
      (node (ref "LED8") (pin "2") (pinfunction "A_2") (pintype "input"))
      (node (ref "R35") (pin "1") (pinfunction "1_1") (pintype "input"))
    )
    (net (code "34") (name "Net-(Q1-Pad1)") (class "Default")
      (node (ref "Q1") (pin "1") (pinfunction "1_1") (pintype "input"))
      (node (ref "R1") (pin "2") (pinfunction "2_2") (pintype "input"))
    )
    (net (code "35") (name "Net-(Q2-Pad1)") (class "Default")
      (node (ref "Q2") (pin "1") (pinfunction "1_1") (pintype "input"))
      (node (ref "R31") (pin "2") (pinfunction "2_2") (pintype "input"))
    )
    (net (code "36") (name "Net-(Q2-Pad3)") (class "Default")
      (node (ref "Q2") (pin "3") (pinfunction "3_3") (pintype "input"))
      (node (ref "R33") (pin "2") (pinfunction "2_2") (pintype "input"))
    )
    (net (code "37") (name "Net-(Q4-Pad1)") (class "Default")
      (node (ref "Q4") (pin "1") (pinfunction "1_1") (pintype "input"))
      (node (ref "R32") (pin "2") (pinfunction "2_2") (pintype "input"))
    )
    (net (code "38") (name "Net-(Q4-Pad3)") (class "Default")
      (node (ref "Q4") (pin "3") (pinfunction "3_3") (pintype "input"))
      (node (ref "R34") (pin "2") (pinfunction "2_2") (pintype "input"))
    )
    (net (code "39") (name "Net-(U1-AVREF)") (class "Default")
      (node (ref "R29") (pin "2") (pinfunction "2_2") (pintype "input"))
      (node (ref "R30") (pin "1") (pinfunction "1_1") (pintype "input"))
      (node (ref "U1") (pin "12") (pinfunction "AVREF_12") (pintype "input"))
      (node (ref "U1") (pin "13") (pinfunction "BVREF_13") (pintype "input"))
    )
    (net (code "40") (name "Net-(U1-CP1)") (class "Default")
      (node (ref "C34") (pin "1") (pinfunction "1_1") (pintype "input"))
      (node (ref "U1") (pin "1") (pinfunction "CP1_1") (pintype "input"))
    )
    (net (code "41") (name "Net-(U1-CP2)") (class "Default")
      (node (ref "C34") (pin "2") (pinfunction "2_2") (pintype "input"))
      (node (ref "U1") (pin "2") (pinfunction "CP2_2") (pintype "input"))
    )
    (net (code "42") (name "Net-(U1-ISENA)") (class "Default")
      (node (ref "R26") (pin "2") (pinfunction "2_2") (pintype "input"))
      (node (ref "U1") (pin "6") (pinfunction "ISENA_6") (pintype "input"))
    )
    (net (code "43") (name "Net-(U1-ISENB)") (class "Default")
      (node (ref "R27") (pin "2") (pinfunction "2_2") (pintype "input"))
      (node (ref "U1") (pin "9") (pinfunction "ISENB_9") (pintype "input"))
    )
    (net (code "44") (name "Net-(U1-VCP)") (class "Default")
      (node (ref "C35") (pin "1") (pinfunction "1_1") (pintype "input"))
      (node (ref "R28") (pin "2") (pinfunction "2_2") (pintype "input"))
      (node (ref "U1") (pin "3") (pinfunction "VCP_3") (pintype "input"))
    )
    (net (code "45") (name "Net-(U11-#RE)") (class "Default")
      (node (ref "Q1") (pin "3") (pinfunction "3_3") (pintype "input"))
      (node (ref "R2") (pin "2") (pinfunction "2_2") (pintype "input"))
      (node (ref "U11") (pin "2") (pinfunction "#RE_2") (pintype "input"))
      (node (ref "U11") (pin "3") (pinfunction "DE_3") (pintype "input"))
    )
    (net (code "46") (name "Net-(U11-A)") (class "Default")
      (node (ref "D2") (pin "1") (pinfunction "1_1") (pintype "input"))
      (node (ref "D3") (pin "2") (pinfunction "2_2") (pintype "input"))
      (node (ref "F2") (pin "1") (pinfunction "1_1") (pintype "input"))
      (node (ref "R4") (pin "1") (pinfunction "1_1") (pintype "input"))
      (node (ref "U11") (pin "6") (pinfunction "A_6") (pintype "input"))
    )
    (net (code "47") (name "Net-(U11-B)") (class "Default")
      (node (ref "D1") (pin "2") (pinfunction "2_2") (pintype "input"))
      (node (ref "D3") (pin "1") (pinfunction "1_1") (pintype "input"))
      (node (ref "F1") (pin "1") (pinfunction "1_1") (pintype "input"))
      (node (ref "R3") (pin "2") (pinfunction "2_2") (pintype "input"))
      (node (ref "U11") (pin "7") (pinfunction "B_7") (pintype "input"))
    )
    (net (code "48") (name "Net-(U12-VCAP1)") (class "Default")
      (node (ref "C30") (pin "2") (pinfunction "2_2") (pintype "input"))
      (node (ref "U12") (pin "30") (pinfunction "VCAP1_30") (pintype "input"))
    )
    (net (code "49") (name "RXD") (class "Default")
      (node (ref "R32") (pin "1") (pinfunction "1_1") (pintype "input"))
      (node (ref "R5") (pin "2") (pinfunction "2_2") (pintype "input"))
      (node (ref "U11") (pin "1") (pinfunction "RO_1") (pintype "input"))
      (node (ref "U12") (pin "43") (pinfunction "PA10_43") (pintype "bidirectional"))
    )
    (net (code "50") (name "Step") (class "Default")
      (node (ref "U1") (pin "22") (pinfunction "STEP_22") (pintype "input"))
      (node (ref "U12") (pin "26") (pinfunction "PB0_26") (pintype "bidirectional"))
    )
    (net (code "51") (name "TXD") (class "Default")
      (node (ref "R1") (pin "1") (pinfunction "1_1") (pintype "input"))
      (node (ref "R31") (pin "1") (pinfunction "1_1") (pintype "input"))
      (node (ref "U12") (pin "42") (pinfunction "PA9_42") (pintype "bidirectional"))
    )
    (net (code "52") (name "VCC3.3") (class "Default")
      (node (ref "C2") (pin "2") (pinfunction "2_2") (pintype "input"))
      (node (ref "C24") (pin "1") (pinfunction "1_1") (pintype "input"))
      (node (ref "C25") (pin "1") (pinfunction "1_1") (pintype "input"))
      (node (ref "C26") (pin "1") (pinfunction "1_1") (pintype "input"))
      (node (ref "C27") (pin "1") (pinfunction "1_1") (pintype "input"))
      (node (ref "C28") (pin "1") (pinfunction "1_1") (pintype "input"))
      (node (ref "C29") (pin "1") (pinfunction "1_1") (pintype "input"))
      (node (ref "C37") (pin "1") (pinfunction "1_1") (pintype "input"))
      (node (ref "C8") (pin "1") (pinfunction "1_1") (pintype "input"))
      (node (ref "Q2") (pin "2") (pinfunction "2_2") (pintype "input"))
      (node (ref "Q4") (pin "2") (pinfunction "2_2") (pintype "input"))
      (node (ref "R2") (pin "1") (pinfunction "1_1") (pintype "input"))
      (node (ref "R35") (pin "2") (pinfunction "2_2") (pintype "input"))
      (node (ref "R4") (pin "2") (pinfunction "2_2") (pintype "input"))
      (node (ref "R5") (pin "1") (pinfunction "1_1") (pintype "input"))
      (node (ref "RN1") (pin "1") (pinfunction "1_1") (pintype "input"))
      (node (ref "RN1") (pin "2") (pinfunction "2_2") (pintype "input"))
      (node (ref "RN1") (pin "3") (pinfunction "3_3") (pintype "input"))
      (node (ref "RN1") (pin "4") (pinfunction "4_4") (pintype "input"))
      (node (ref "RN2") (pin "1") (pinfunction "1_1") (pintype "input"))
      (node (ref "RN2") (pin "2") (pinfunction "2_2") (pintype "input"))
      (node (ref "RN2") (pin "3") (pinfunction "3_3") (pintype "input"))
      (node (ref "RN2") (pin "4") (pinfunction "4_4") (pintype "input"))
      (node (ref "U1") (pin "16") (pinfunction "nRESET_16") (pintype "input"))
      (node (ref "U1") (pin "17") (pinfunction "nSLEEP_17") (pintype "input"))
      (node (ref "U1") (pin "25") (pinfunction "MODE1_25") (pintype "input"))
      (node (ref "U11") (pin "8") (pinfunction "VCC_8") (pintype "input"))
      (node (ref "U12") (pin "1") (pinfunction "VBAT_1") (pintype "input"))
      (node (ref "U12") (pin "13") (pinfunction "VDDAVREF+_13") (pintype "input"))
      (node (ref "U12") (pin "19") (pinfunction "VDD_19") (pintype "input"))
      (node (ref "U12") (pin "32") (pinfunction "VDD_32") (pintype "input"))
      (node (ref "U12") (pin "48") (pinfunction "VDD_48") (pintype "input"))
      (node (ref "U12") (pin "64") (pinfunction "VDD_64") (pintype "input"))
      (node (ref "U3") (pin "2") (pinfunction "VOUT_2") (pintype "input"))
      (node (ref "X1") (pin "4") (pinfunction "VDD_4") (pintype "input"))
      (node (ref "X5") (pin "4") (pinfunction "VDD_4") (pintype "input"))
    )
    (net (code "53") (name "unconnected-(U1-DECAY-Pad19)") (class "Default")
      (node (ref "U1") (pin "19") (pinfunction "DECAY_19") (pintype "input+no_connect"))
    )
    (net (code "54") (name "unconnected-(U1-NC-Pad23)") (class "Default")
      (node (ref "U1") (pin "23") (pinfunction "NC_23") (pintype "input+no_connect"))
    )
    (net (code "55") (name "unconnected-(U1-nFAULT-Pad18)") (class "Default")
      (node (ref "U1") (pin "18") (pinfunction "nFAULT_18") (pintype "input+no_connect"))
    )
    (net (code "56") (name "unconnected-(U1-nHOME-Pad27)") (class "Default")
      (node (ref "U1") (pin "27") (pinfunction "nHOME_27") (pintype "input+no_connect"))
    )
    (net (code "57") (name "unconnected-(U12-PA0-WKUP-Pad14)") (class "Default")
      (node (ref "U12") (pin "14") (pinfunction "PA0-WKUP_14") (pintype "bidirectional"))
    )
    (net (code "58") (name "unconnected-(U12-PA1-Pad15)") (class "Default")
      (node (ref "U12") (pin "15") (pinfunction "PA1_15") (pintype "bidirectional"))
    )
    (net (code "59") (name "unconnected-(U12-PA2-Pad16)") (class "Default")
      (node (ref "U12") (pin "16") (pinfunction "PA2_16") (pintype "bidirectional"))
    )
    (net (code "60") (name "unconnected-(U12-PA3-Pad17)") (class "Default")
      (node (ref "U12") (pin "17") (pinfunction "PA3_17") (pintype "bidirectional"))
    )
    (net (code "61") (name "unconnected-(U12-PA4-Pad20)") (class "Default")
      (node (ref "U12") (pin "20") (pinfunction "PA4_20") (pintype "bidirectional"))
    )
    (net (code "62") (name "unconnected-(U12-PA5-Pad21)") (class "Default")
      (node (ref "U12") (pin "21") (pinfunction "PA5_21") (pintype "bidirectional"))
    )
    (net (code "63") (name "unconnected-(U12-PA6-Pad22)") (class "Default")
      (node (ref "U12") (pin "22") (pinfunction "PA6_22") (pintype "bidirectional"))
    )
    (net (code "64") (name "unconnected-(U12-PA7-Pad23)") (class "Default")
      (node (ref "U12") (pin "23") (pinfunction "PA7_23") (pintype "bidirectional"))
    )
    (net (code "65") (name "unconnected-(U12-PA8-Pad41)") (class "Default")
      (node (ref "U12") (pin "41") (pinfunction "PA8_41") (pintype "bidirectional"))
    )
    (net (code "66") (name "unconnected-(U12-PA11-Pad44)") (class "Default")
      (node (ref "U12") (pin "44") (pinfunction "PA11_44") (pintype "bidirectional"))
    )
    (net (code "67") (name "unconnected-(U12-PA12-Pad45)") (class "Default")
      (node (ref "U12") (pin "45") (pinfunction "PA12_45") (pintype "bidirectional"))
    )
    (net (code "68") (name "unconnected-(U12-PA15-Pad50)") (class "Default")
      (node (ref "U12") (pin "50") (pinfunction "PA15_50") (pintype "bidirectional"))
    )
    (net (code "69") (name "unconnected-(U12-PB1-Pad27)") (class "Default")
      (node (ref "U12") (pin "27") (pinfunction "PB1_27") (pintype "bidirectional"))
    )
    (net (code "70") (name "unconnected-(U12-PB2-Pad28)") (class "Default")
      (node (ref "U12") (pin "28") (pinfunction "PB2_28") (pintype "bidirectional"))
    )
    (net (code "71") (name "unconnected-(U12-PB10-Pad29)") (class "Default")
      (node (ref "U12") (pin "29") (pinfunction "PB10_29") (pintype "bidirectional"))
    )
    (net (code "72") (name "unconnected-(U12-PB12-Pad33)") (class "Default")
      (node (ref "U12") (pin "33") (pinfunction "PB12_33") (pintype "bidirectional"))
    )
    (net (code "73") (name "unconnected-(U12-PB13-Pad34)") (class "Default")
      (node (ref "U12") (pin "34") (pinfunction "PB13_34") (pintype "bidirectional"))
    )
    (net (code "74") (name "unconnected-(U12-PB14-Pad35)") (class "Default")
      (node (ref "U12") (pin "35") (pinfunction "PB14_35") (pintype "bidirectional"))
    )
    (net (code "75") (name "unconnected-(U12-PB15-Pad36)") (class "Default")
      (node (ref "U12") (pin "36") (pinfunction "PB15_36") (pintype "bidirectional"))
    )
    (net (code "76") (name "unconnected-(U12-PC0-Pad8)") (class "Default")
      (node (ref "U12") (pin "8") (pinfunction "PC0_8") (pintype "bidirectional"))
    )
    (net (code "77") (name "unconnected-(U12-PC1-Pad9)") (class "Default")
      (node (ref "U12") (pin "9") (pinfunction "PC1_9") (pintype "bidirectional"))
    )
    (net (code "78") (name "unconnected-(U12-PC2-Pad10)") (class "Default")
      (node (ref "U12") (pin "10") (pinfunction "PC2_10") (pintype "bidirectional"))
    )
    (net (code "79") (name "unconnected-(U12-PC3-Pad11)") (class "Default")
      (node (ref "U12") (pin "11") (pinfunction "PC3_11") (pintype "bidirectional"))
    )
    (net (code "80") (name "unconnected-(U12-PC6-Pad37)") (class "Default")
      (node (ref "U12") (pin "37") (pinfunction "PC6_37") (pintype "bidirectional"))
    )
    (net (code "81") (name "unconnected-(U12-PC7-Pad38)") (class "Default")
      (node (ref "U12") (pin "38") (pinfunction "PC7_38") (pintype "bidirectional"))
    )
    (net (code "82") (name "unconnected-(U12-PC8-Pad39)") (class "Default")
      (node (ref "U12") (pin "39") (pinfunction "PC8_39") (pintype "bidirectional"))
    )
    (net (code "83") (name "unconnected-(U12-PC9-Pad40)") (class "Default")
      (node (ref "U12") (pin "40") (pinfunction "PC9_40") (pintype "bidirectional"))
    )
    (net (code "84") (name "unconnected-(U12-PC10-Pad51)") (class "Default")
      (node (ref "U12") (pin "51") (pinfunction "PC10_51") (pintype "bidirectional"))
    )
    (net (code "85") (name "unconnected-(U12-PC13-ANTI_TAMP-Pad2)") (class "Default")
      (node (ref "U12") (pin "2") (pinfunction "PC13-ANTI_TAMP_2") (pintype "bidirectional"))
    )
    (net (code "86") (name "unconnected-(U12-PC15-OSC32_OUT-Pad4)") (class "Default")
      (node (ref "U12") (pin "4") (pinfunction "PC15-OSC32_OUT_4") (pintype "bidirectional"))
    )
    (net (code "87") (name "unconnected-(U12-PH1-OSC_OUT-Pad6)") (class "Default")
      (node (ref "U12") (pin "6") (pinfunction "PH1-OSC_OUT_6") (pintype "bidirectional"))
    )
    (net (code "88") (name "unconnected-(X1-Tri-state-Pad1)") (class "Default")
      (node (ref "X1") (pin "1") (pinfunction "Tri-state_1") (pintype "input"))
    )
    (net (code "89") (name "unconnected-(X5-Tri-state-Pad1)") (class "Default")
      (node (ref "X5") (pin "1") (pinfunction "Tri-state_1") (pintype "input"))
    )
  )
)
